# IO_Peripherals.net
KiCad netlist of a schematic drawn in Altium Designer
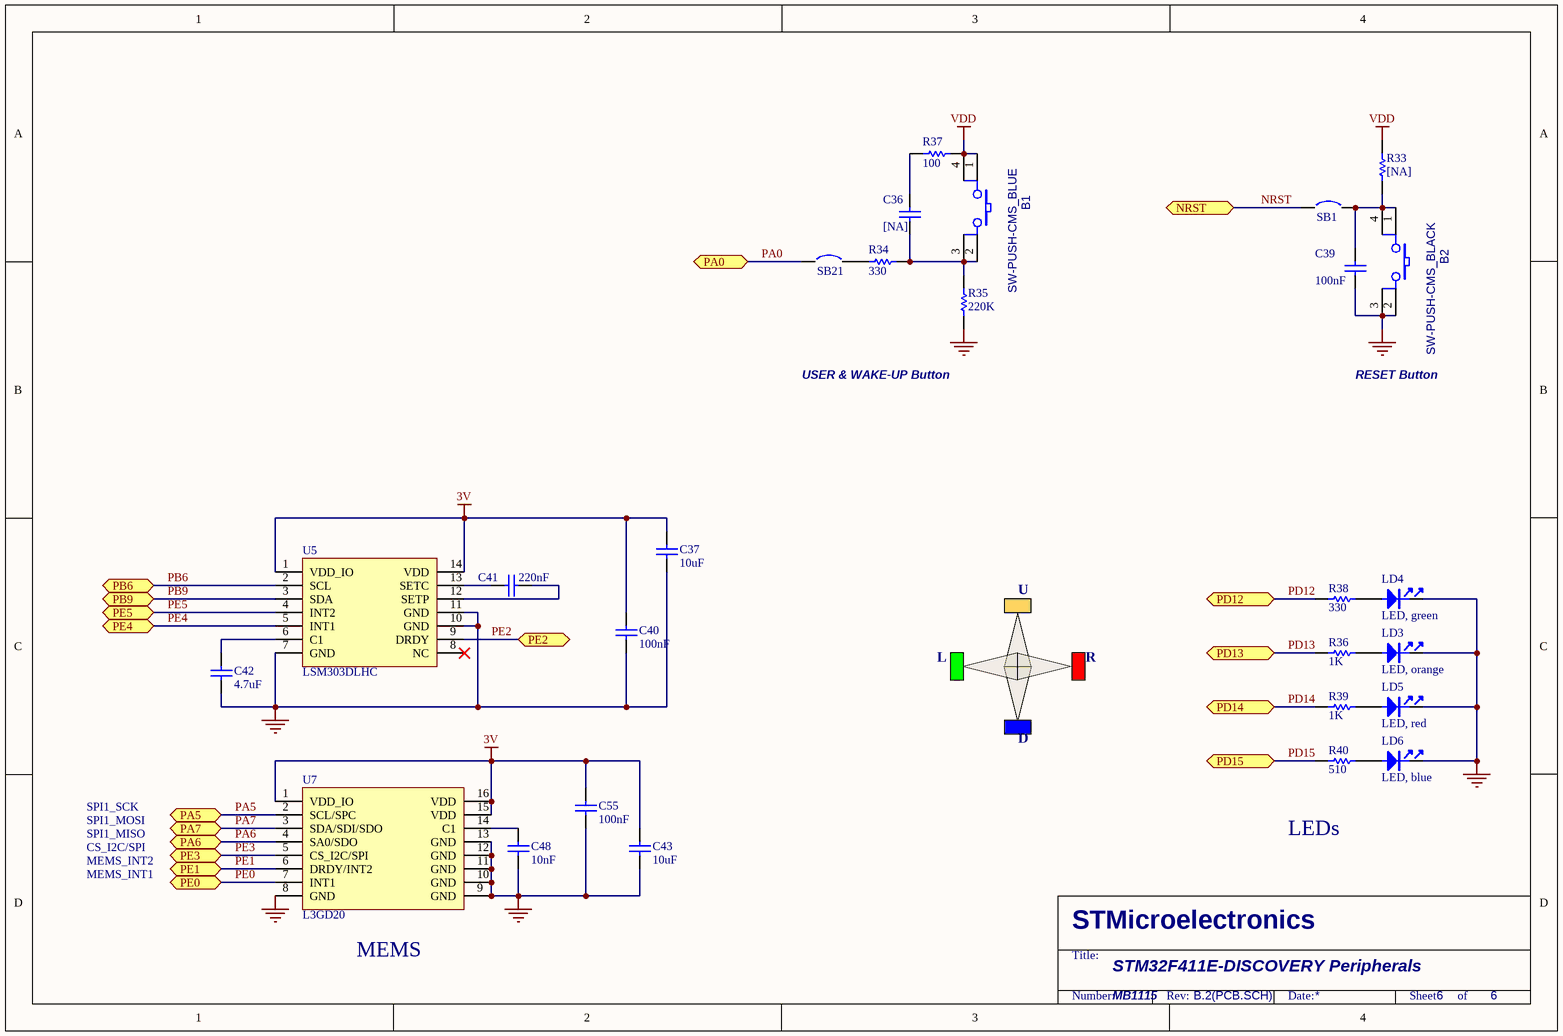
[diagram p0: IO Peripherals.SchDoc]

(export (version "E")
  (design (tool "Eeschema 10.0.6"))
  (components
    (comp (ref "B1")
      (value "SW-PUSH-CMS_BLUE")
      (footprint "STM-SMEE:BP1CMS")
      (description "Non-Open Push Button,Blue 0.1A 24V,Square head,6*6,SMT,180Degree,TD-0341X-GO1,wealthmetal")
      (libsource (lib "MCD_TOOLS") (part "SW-PUSH-CMS_BLUE"))
    )
    (comp (ref "B2")
      (value "SW-PUSH-CMS_BLACK")
      (footprint "STM-SMEE:BP1CMS")
      (description "Non-Open Push Button,Black 0.1A 24V,Square head,6*6,SMT,180Degree,TD-0341X-GO1,wealthmetal")
      (libsource (lib "MCD_TOOLS") (part "SW-PUSH-CMS_BLACK"))
    )
    (comp (ref "C36")
      (value "[NA]")
      (footprint "0402C")
      (description "Capacitor,NA,0402")
      (libsource (lib "MCD_TOOLS") (part "Cap_NA_0402"))
    )
    (comp (ref "C37")
      (value "10uF")
      (footprint "0603C")
      (description "Capacitor,10uF,6.3V,X5R,20%,0603,YAGEO")
      (libsource (lib "MCD_TOOLS") (part "Cap_10uF_X5R_10%_0603"))
    )
    (comp (ref "C39")
      (value "100nF")
      (footprint "0402C")
      (description "Capacitor,100nF,16V,X7R,10%,0402,YAGEO")
      (libsource (lib "MCD_TOOLS") (part "Cap_100nF_X7R_10%_0402"))
    )
    (comp (ref "C40")
      (value "100nF")
      (footprint "0402C")
      (description "Capacitor,100nF,16V,X7R,10%,0402,YAGEO")
      (libsource (lib "MCD_TOOLS") (part "Cap_100nF_X7R_10%_0402"))
    )
    (comp (ref "C41")
      (value "220nF")
      (footprint "0603C")
      (description "Capacitor,220nF,16V,X7R,10%,0603,YAGEO")
      (libsource (lib "MCD_TOOLS") (part "Cap_220nF_X7R_10%_0603"))
    )
    (comp (ref "C42")
      (value "4.7uF")
      (footprint "0603C")
      (description "Capacitor,4.7uF,16V, X5R,10%,0603,YAGEO")
      (libsource (lib "MCD_TOOLS") (part "Cap_4.7uF_X5R_10%_0603"))
    )
    (comp (ref "C43")
      (value "10uF")
      (footprint "0603C")
      (description "Capacitor,10uF,6.3V,X5R,20%,0603,YAGEO")
      (libsource (lib "MCD_TOOLS") (part "Cap_10uF_X5R_10%_0603"))
    )
    (comp (ref "C48")
      (value "10nF")
      (footprint "0603C")
      (description "Capacitor,10nF,50V,X7R,10%,0603,YAGEO")
      (libsource (lib "MCD_TOOLS") (part "Cap_10nF_X7R_10%_0603"))
    )
    (comp (ref "C55")
      (value "100nF")
      (footprint "0402C")
      (description "Capacitor,100nF,16V,X7R,10%,0402,YAGEO")
      (libsource (lib "MCD_TOOLS") (part "Cap_100nF_X7R_10%_0402"))
    )
    (comp (ref "LD3")
      (value "LED, orange")
      (footprint "0603D")
      (description "LED,orange,0603,19-217/S2C-AM2N2VY/3T,everlight")
      (libsource (lib "MCD_TOOLS") (part "LED_orange"))
    )
    (comp (ref "LD4")
      (value "LED, green")
      (footprint "0603D")
      (description "LED,green,0603,19-213SYGC/S530-E2/TR8,everlight")
      (libsource (lib "MCD_TOOLS") (part "LED_green"))
    )
    (comp (ref "LD5")
      (value "LED, red")
      (footprint "0603D")
      (description "LED,red,0603,19-213-R6C-AP1Q2B/3T,everlight")
      (libsource (lib "MCD_TOOLS") (part "LED_red"))
    )
    (comp (ref "LD6")
      (value "LED, blue")
      (footprint "0603D")
      (description "LED,Blue,0603,19-217/BHC-ZL1M2RY/3T,everlight")
      (libsource (lib "MCD_TOOLS") (part "LED_blue"))
    )
    (comp (ref "R33")
      (value "[NA]")
      (footprint "STM-SMEE:0402R")
      (description "Resistor,[NA],0402")
      (libsource (lib "MCD_TOOLS") (part "Res_NA_0402"))
    )
    (comp (ref "R34")
      (value "330")
      (footprint "0402R")
      (description "Resistor")
      (fields (field (name "PUBLISHER") "Altium Limited"))
      (libsource (lib "Miscellaneous Devices") (part "res1"))
    )
    (comp (ref "R35")
      (value "220K")
      (footprint "0402R")
      (description "Resistor")
      (fields (field (name "PUBLISHER") "Altium Limited"))
      (libsource (lib "Miscellaneous Devices") (part "res1"))
    )
    (comp (ref "R36")
      (value "1K")
      (footprint "0402R")
      (description "Resistor")
      (fields (field (name "PUBLISHER") "Altium Limited"))
      (libsource (lib "Miscellaneous Devices") (part "Res1"))
    )
    (comp (ref "R37")
      (value "100")
      (footprint "0402R")
      (description "Resistor")
      (fields (field (name "PUBLISHER") "Altium Limited"))
      (libsource (lib "Miscellaneous Devices") (part "res1"))
    )
    (comp (ref "R38")
      (value "330")
      (footprint "0402R")
      (description "Resistor")
      (fields (field (name "PUBLISHER") "Altium Limited"))
      (libsource (lib "Miscellaneous Devices") (part "Res1"))
    )
    (comp (ref "R39")
      (value "1K")
      (footprint "0402R")
      (description "Resistor")
      (fields (field (name "PUBLISHER") "Altium Limited"))
      (libsource (lib "Miscellaneous Devices") (part "Res1"))
    )
    (comp (ref "R40")
      (value "510")
      (footprint "0402R")
      (description "Resistor")
      (fields (field (name "PUBLISHER") "Altium Limited"))
      (libsource (lib "Miscellaneous Devices") (part "Res1"))
    )
    (comp (ref "SB1")
      (value "Circuit Breaker")
      (footprint "JP2_SMD")
      (libsource (lib "MCD_TOOLS") (part "Circuit Breaker"))
    )
    (comp (ref "SB21")
      (value "Circuit Breaker")
      (footprint "JP2_SMD")
      (libsource (lib "MCD_TOOLS") (part "Circuit Breaker"))
    )
    (comp (ref "U5")
      (value "LSM303DLHC")
      (footprint "LGA14(3*5)")
      (description "Ultra compact high performance e-compass 3D accelerometer and 3D magnetometer module")
      (libsource (lib "MCD_TOOLS") (part "LSM303DLHC"))
    )
    (comp (ref "U7")
      (value "L3GD20")
      (footprint "STM-SMEE:LGA16-4x4")
      (description "MEMS motion sensor three-axis digital output gyroscopeelerometer")
      (libsource (lib "MCD_TOOLS") (part "L3GD20"))
    )
  )
  (nets
    (net (code "1") (name "/NRST") (class "Default")
      (node (ref "SB1") (pin "1") (pinfunction "1_1") (pintype "passive"))
    )
    (net (code "2") (name "/PA0") (class "Default")
      (node (ref "SB21") (pin "1") (pinfunction "1_1") (pintype "passive"))
    )
    (net (code "3") (name "/PA5") (class "Default")
      (node (ref "U7") (pin "2") (pinfunction "SCL/SPC_2") (pintype "passive"))
    )
    (net (code "4") (name "/PA6") (class "Default")
      (node (ref "U7") (pin "4") (pinfunction "SA0/SDO_4") (pintype "passive"))
    )
    (net (code "5") (name "/PA7") (class "Default")
      (node (ref "U7") (pin "3") (pinfunction "SDA/SDI/SDO_3") (pintype "passive"))
    )
    (net (code "6") (name "/PB6") (class "Default")
      (node (ref "U5") (pin "2") (pinfunction "SCL_2") (pintype "passive"))
    )
    (net (code "7") (name "/PB9") (class "Default")
      (node (ref "U5") (pin "3") (pinfunction "SDA_3") (pintype "passive"))
    )
    (net (code "8") (name "/PD12") (class "Default")
      (node (ref "R38") (pin "2") (pinfunction "2_2") (pintype "passive"))
    )
    (net (code "9") (name "/PD13") (class "Default")
      (node (ref "R36") (pin "2") (pinfunction "2_2") (pintype "passive"))
    )
    (net (code "10") (name "/PD14") (class "Default")
      (node (ref "R39") (pin "2") (pinfunction "2_2") (pintype "passive"))
    )
    (net (code "11") (name "/PD15") (class "Default")
      (node (ref "R40") (pin "2") (pinfunction "2_2") (pintype "passive"))
    )
    (net (code "12") (name "/PE0") (class "Default")
      (node (ref "U7") (pin "7") (pinfunction "INT1_7") (pintype "passive"))
    )
    (net (code "13") (name "/PE1") (class "Default")
      (node (ref "U7") (pin "6") (pinfunction "DRDY/INT2_6") (pintype "passive"))
    )
    (net (code "14") (name "/PE2") (class "Default")
      (node (ref "U5") (pin "9") (pinfunction "DRDY_9") (pintype "passive"))
    )
    (net (code "15") (name "/PE3") (class "Default")
      (node (ref "U7") (pin "5") (pinfunction "CS_I2C/SPI_5") (pintype "passive"))
    )
    (net (code "16") (name "/PE4") (class "Default")
      (node (ref "U5") (pin "5") (pinfunction "INT1_5") (pintype "passive"))
    )
    (net (code "17") (name "/PE5") (class "Default")
      (node (ref "U5") (pin "4") (pinfunction "INT2_4") (pintype "passive"))
    )
    (net (code "18") (name "3V") (class "Default")
      (node (ref "C37") (pin "2") (pinfunction "2_2") (pintype "passive"))
      (node (ref "C40") (pin "2") (pinfunction "2_2") (pintype "passive"))
      (node (ref "C43") (pin "2") (pinfunction "2_2") (pintype "passive"))
      (node (ref "C55") (pin "2") (pinfunction "2_2") (pintype "passive"))
      (node (ref "U5") (pin "1") (pinfunction "VDD_IO_1") (pintype "passive"))
      (node (ref "U5") (pin "14") (pinfunction "VDD_14") (pintype "passive"))
      (node (ref "U7") (pin "1") (pinfunction "VDD_IO_1") (pintype "passive"))
      (node (ref "U7") (pin "15") (pinfunction "VDD_15") (pintype "passive"))
      (node (ref "U7") (pin "16") (pinfunction "VDD_16") (pintype "passive"))
    )
    (net (code "19") (name "GND") (class "Default")
      (node (ref "B2") (pin "2") (pinfunction "2_2") (pintype "passive"))
      (node (ref "B2") (pin "3") (pinfunction "3_3") (pintype "passive"))
      (node (ref "C37") (pin "1") (pinfunction "1_1") (pintype "passive"))
      (node (ref "C39") (pin "1") (pinfunction "1_1") (pintype "passive"))
      (node (ref "C40") (pin "1") (pinfunction "1_1") (pintype "passive"))
      (node (ref "C42") (pin "1") (pinfunction "1_1") (pintype "passive"))
      (node (ref "C43") (pin "1") (pinfunction "1_1") (pintype "passive"))
      (node (ref "C48") (pin "1") (pinfunction "1_1") (pintype "passive"))
      (node (ref "C55") (pin "1") (pinfunction "1_1") (pintype "passive"))
      (node (ref "LD3") (pin "2") (pintype "passive"))
      (node (ref "LD4") (pin "2") (pintype "passive"))
      (node (ref "LD5") (pin "2") (pintype "passive"))
      (node (ref "LD6") (pin "2") (pintype "passive"))
      (node (ref "R35") (pin "1") (pinfunction "1_1") (pintype "passive"))
      (node (ref "U5") (pin "10") (pinfunction "GND_10") (pintype "passive"))
      (node (ref "U5") (pin "11") (pinfunction "GND_11") (pintype "passive"))
      (node (ref "U5") (pin "7") (pinfunction "GND_7") (pintype "passive"))
      (node (ref "U7") (pin "10") (pinfunction "GND_10") (pintype "passive"))
      (node (ref "U7") (pin "11") (pinfunction "GND_11") (pintype "passive"))
      (node (ref "U7") (pin "12") (pinfunction "GND_12") (pintype "passive"))
      (node (ref "U7") (pin "13") (pinfunction "GND_13") (pintype "passive"))
      (node (ref "U7") (pin "8") (pinfunction "GND_8") (pintype "passive"))
      (node (ref "U7") (pin "9") (pinfunction "GND_9") (pintype "passive"))
    )
    (net (code "20") (name "Net-(B1-Pad2)") (class "Default")
      (node (ref "B1") (pin "2") (pinfunction "2_2") (pintype "passive"))
      (node (ref "B1") (pin "3") (pinfunction "3_3") (pintype "passive"))
      (node (ref "C36") (pin "1") (pinfunction "1_1") (pintype "passive"))
      (node (ref "R34") (pin "2") (pinfunction "2_2") (pintype "passive"))
      (node (ref "R35") (pin "2") (pinfunction "2_2") (pintype "passive"))
    )
    (net (code "21") (name "Net-(B2-Pad1)") (class "Default")
      (node (ref "B2") (pin "1") (pinfunction "1_1") (pintype "passive"))
      (node (ref "B2") (pin "4") (pinfunction "4_4") (pintype "passive"))
      (node (ref "C39") (pin "2") (pinfunction "2_2") (pintype "passive"))
      (node (ref "R33") (pin "1") (pinfunction "1_1") (pintype "passive"))
      (node (ref "SB1") (pin "2") (pinfunction "2_2") (pintype "passive"))
    )
    (net (code "22") (name "Net-(C36-Pad2)") (class "Default")
      (node (ref "C36") (pin "2") (pinfunction "2_2") (pintype "passive"))
      (node (ref "R37") (pin "1") (pinfunction "1_1") (pintype "passive"))
    )
    (net (code "23") (name "Net-(LD3-Pad1)") (class "Default")
      (node (ref "LD3") (pin "1") (pintype "passive"))
      (node (ref "R36") (pin "1") (pinfunction "1_1") (pintype "passive"))
    )
    (net (code "24") (name "Net-(LD4-Pad1)") (class "Default")
      (node (ref "LD4") (pin "1") (pintype "passive"))
      (node (ref "R38") (pin "1") (pinfunction "1_1") (pintype "passive"))
    )
    (net (code "25") (name "Net-(LD5-Pad1)") (class "Default")
      (node (ref "LD5") (pin "1") (pintype "passive"))
      (node (ref "R39") (pin "1") (pinfunction "1_1") (pintype "passive"))
    )
    (net (code "26") (name "Net-(LD6-Pad1)") (class "Default")
      (node (ref "LD6") (pin "1") (pintype "passive"))
      (node (ref "R40") (pin "1") (pinfunction "1_1") (pintype "passive"))
    )
    (net (code "27") (name "Net-(R34-Pad1)") (class "Default")
      (node (ref "R34") (pin "1") (pinfunction "1_1") (pintype "passive"))
      (node (ref "SB21") (pin "2") (pinfunction "2_2") (pintype "passive"))
    )
    (net (code "28") (name "Net-(U5-C1)") (class "Default")
      (node (ref "C42") (pin "2") (pinfunction "2_2") (pintype "passive"))
      (node (ref "U5") (pin "6") (pinfunction "C1_6") (pintype "passive"))
    )
    (net (code "29") (name "Net-(U5-SETC)") (class "Default")
      (node (ref "C41") (pin "1") (pinfunction "1_1") (pintype "passive"))
      (node (ref "U5") (pin "13") (pinfunction "SETC_13") (pintype "passive"))
    )
    (net (code "30") (name "Net-(U5-SETP)") (class "Default")
      (node (ref "C41") (pin "2") (pinfunction "2_2") (pintype "passive"))
      (node (ref "U5") (pin "12") (pinfunction "SETP_12") (pintype "passive"))
    )
    (net (code "31") (name "Net-(U7-C1)") (class "Default")
      (node (ref "C48") (pin "2") (pinfunction "2_2") (pintype "passive"))
      (node (ref "U7") (pin "14") (pinfunction "C1_14") (pintype "passive"))
    )
    (net (code "32") (name "VDD") (class "Default")
      (node (ref "B1") (pin "1") (pinfunction "1_1") (pintype "passive"))
      (node (ref "B1") (pin "4") (pinfunction "4_4") (pintype "passive"))
      (node (ref "R33") (pin "2") (pinfunction "2_2") (pintype "passive"))
      (node (ref "R37") (pin "2") (pinfunction "2_2") (pintype "passive"))
    )
    (net (code "33") (name "unconnected-(U5-NC-Pad8)") (class "Default")
      (node (ref "U5") (pin "8") (pinfunction "NC_8") (pintype "passive+no_connect"))
    )
  )
)
